# v1.net
KiCad netlist of a schematic drawn in EAGLE
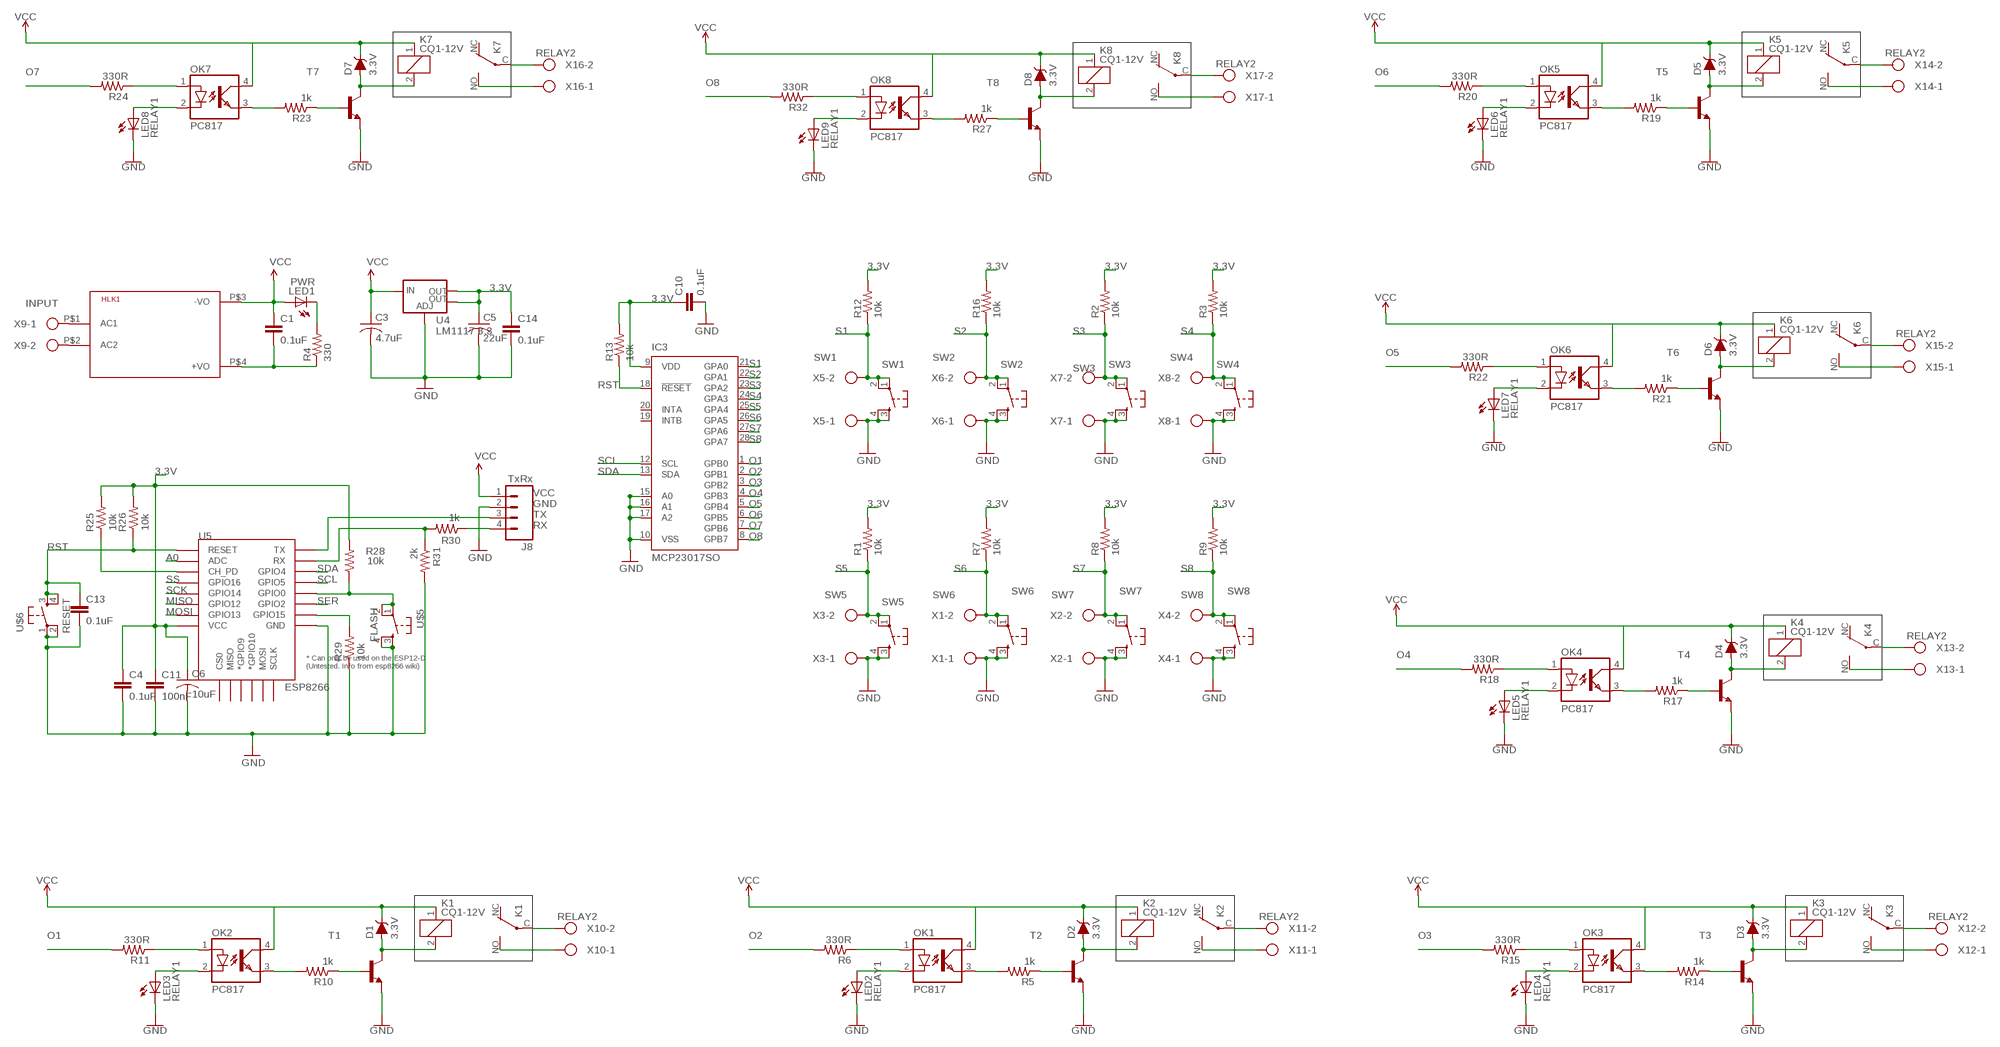
[diagram p0: schematic, sheet 1]

(export (version "E")
  (design (tool "Eeschema 10.0.6"))
  (components
    (comp (ref "C1")
      (value "0.1uF")
      (footprint "eagle-import:0805")
      (libsource (lib "eagle-import") (part "CAP0805"))
    )
    (comp (ref "C3")
      (value "4.7uF")
      (footprint "eagle-import:C1206")
      (libsource (lib "eagle-import") (part "C-USC1206"))
    )
    (comp (ref "C4")
      (value "0.1uF")
      (footprint "eagle-import:0805")
      (libsource (lib "eagle-import") (part "CAP0805"))
    )
    (comp (ref "C5")
      (value "22uF")
      (footprint "eagle-import:C1206")
      (libsource (lib "eagle-import") (part "C-USC1206"))
    )
    (comp (ref "C6")
      (value "10uF")
      (footprint "eagle-import:C1206")
      (libsource (lib "eagle-import") (part "C-USC1206"))
    )
    (comp (ref "C10")
      (value "0.1uF")
      (footprint "eagle-import:0805")
      (libsource (lib "eagle-import") (part "CAP0805"))
    )
    (comp (ref "C11")
      (value "100nF")
      (footprint "eagle-import:0805")
      (libsource (lib "eagle-import") (part "CAP0805"))
    )
    (comp (ref "C13")
      (value "0.1uF")
      (footprint "eagle-import:0805")
      (libsource (lib "eagle-import") (part "CAP0805"))
    )
    (comp (ref "C14")
      (value "0.1uF")
      (footprint "eagle-import:0805")
      (libsource (lib "eagle-import") (part "CAP0805"))
    )
    (comp (ref "D1")
      (value "3.3V")
      (footprint "eagle-import:SOD-323")
      (libsource (lib "eagle-import") (part "DIODE-ZENER-MM3Z3V3T1G"))
    )
    (comp (ref "D2")
      (value "3.3V")
      (footprint "eagle-import:SOD-323")
      (libsource (lib "eagle-import") (part "DIODE-ZENER-MM3Z3V3T1G"))
    )
    (comp (ref "D3")
      (value "3.3V")
      (footprint "eagle-import:SOD-323")
      (libsource (lib "eagle-import") (part "DIODE-ZENER-MM3Z3V3T1G"))
    )
    (comp (ref "D4")
      (value "3.3V")
      (footprint "eagle-import:SOD-323")
      (libsource (lib "eagle-import") (part "DIODE-ZENER-MM3Z3V3T1G"))
    )
    (comp (ref "D5")
      (value "3.3V")
      (footprint "eagle-import:SOD-323")
      (libsource (lib "eagle-import") (part "DIODE-ZENER-MM3Z3V3T1G"))
    )
    (comp (ref "D6")
      (value "3.3V")
      (footprint "eagle-import:SOD-323")
      (libsource (lib "eagle-import") (part "DIODE-ZENER-MM3Z3V3T1G"))
    )
    (comp (ref "D7")
      (value "3.3V")
      (footprint "eagle-import:SOD-323")
      (libsource (lib "eagle-import") (part "DIODE-ZENER-MM3Z3V3T1G"))
    )
    (comp (ref "D8")
      (value "3.3V")
      (footprint "eagle-import:SOD-323")
      (libsource (lib "eagle-import") (part "DIODE-ZENER-MM3Z3V3T1G"))
    )
    (comp (ref "HLK1")
      (value "HLK-PM013W")
      (footprint "eagle-import:HLK-PM01")
      (libsource (lib "eagle-import") (part "HLK-PM013W"))
    )
    (comp (ref "IC3")
      (value "MCP23017SO")
      (footprint "eagle-import:SO28W")
      (fields (field (name "MF") "MICROCHIP") (field (name "MPN") "MCP23017-E/SO"))
      (libsource (lib "eagle-import") (part "MCP23017SO"))
    )
    (comp (ref "J8")
      (value "TxRx")
      (footprint "eagle-import:MOLEX-1X4")
      (libsource (lib "eagle-import") (part "M04POLAR"))
    )
    (comp (ref "K1")
      (value "CQ1-12V")
      (footprint "eagle-import:CQ1")
      (libsource (lib "eagle-import") (part "CQ1-12V"))
    )
    (comp (ref "K2")
      (value "CQ1-12V")
      (footprint "eagle-import:CQ1")
      (libsource (lib "eagle-import") (part "CQ1-12V"))
    )
    (comp (ref "K3")
      (value "CQ1-12V")
      (footprint "eagle-import:CQ1")
      (libsource (lib "eagle-import") (part "CQ1-12V"))
    )
    (comp (ref "K4")
      (value "CQ1-12V")
      (footprint "eagle-import:CQ1")
      (libsource (lib "eagle-import") (part "CQ1-12V"))
    )
    (comp (ref "K5")
      (value "CQ1-12V")
      (footprint "eagle-import:CQ1")
      (libsource (lib "eagle-import") (part "CQ1-12V"))
    )
    (comp (ref "K6")
      (value "CQ1-12V")
      (footprint "eagle-import:CQ1")
      (libsource (lib "eagle-import") (part "CQ1-12V"))
    )
    (comp (ref "K7")
      (value "CQ1-12V")
      (footprint "eagle-import:CQ1")
      (libsource (lib "eagle-import") (part "CQ1-12V"))
    )
    (comp (ref "K8")
      (value "CQ1-12V")
      (footprint "eagle-import:CQ1")
      (libsource (lib "eagle-import") (part "CQ1-12V"))
    )
    (comp (ref "LED1")
      (value "PWR")
      (footprint "eagle-import:CHIP-LED0805")
      (libsource (lib "eagle-import") (part "LEDCHIP-LED0805"))
    )
    (comp (ref "LED2")
      (value "RELAY1")
      (footprint "eagle-import:CHIP-LED0805")
      (libsource (lib "eagle-import") (part "LEDCHIP-LED0805"))
    )
    (comp (ref "LED3")
      (value "RELAY1")
      (footprint "eagle-import:CHIP-LED0805")
      (libsource (lib "eagle-import") (part "LEDCHIP-LED0805"))
    )
    (comp (ref "LED4")
      (value "RELAY1")
      (footprint "eagle-import:CHIP-LED0805")
      (libsource (lib "eagle-import") (part "LEDCHIP-LED0805"))
    )
    (comp (ref "LED5")
      (value "RELAY1")
      (footprint "eagle-import:CHIP-LED0805")
      (libsource (lib "eagle-import") (part "LEDCHIP-LED0805"))
    )
    (comp (ref "LED6")
      (value "RELAY1")
      (footprint "eagle-import:CHIP-LED0805")
      (libsource (lib "eagle-import") (part "LEDCHIP-LED0805"))
    )
    (comp (ref "LED7")
      (value "RELAY1")
      (footprint "eagle-import:CHIP-LED0805")
      (libsource (lib "eagle-import") (part "LEDCHIP-LED0805"))
    )
    (comp (ref "LED8")
      (value "RELAY1")
      (footprint "eagle-import:CHIP-LED0805")
      (libsource (lib "eagle-import") (part "LEDCHIP-LED0805"))
    )
    (comp (ref "LED9")
      (value "RELAY1")
      (footprint "eagle-import:CHIP-LED0805")
      (libsource (lib "eagle-import") (part "LEDCHIP-LED0805"))
    )
    (comp (ref "OK1")
      (value "PC817")
      (footprint "eagle-import:DIL04")
      (fields (field (name "MPN") "PC817X4J000F"))
      (libsource (lib "eagle-import") (part "PC817"))
    )
    (comp (ref "OK2")
      (value "PC817")
      (footprint "eagle-import:DIL04")
      (fields (field (name "MPN") "PC817X4J000F"))
      (libsource (lib "eagle-import") (part "PC817"))
    )
    (comp (ref "OK3")
      (value "PC817")
      (footprint "eagle-import:DIL04")
      (fields (field (name "MPN") "PC817X4J000F"))
      (libsource (lib "eagle-import") (part "PC817"))
    )
    (comp (ref "OK4")
      (value "PC817")
      (footprint "eagle-import:DIL04")
      (fields (field (name "MPN") "PC817X4J000F"))
      (libsource (lib "eagle-import") (part "PC817"))
    )
    (comp (ref "OK5")
      (value "PC817")
      (footprint "eagle-import:DIL04")
      (fields (field (name "MPN") "PC817X4J000F"))
      (libsource (lib "eagle-import") (part "PC817"))
    )
    (comp (ref "OK6")
      (value "PC817")
      (footprint "eagle-import:DIL04")
      (fields (field (name "MPN") "PC817X4J000F"))
      (libsource (lib "eagle-import") (part "PC817"))
    )
    (comp (ref "OK7")
      (value "PC817")
      (footprint "eagle-import:DIL04")
      (fields (field (name "MPN") "PC817X4J000F"))
      (libsource (lib "eagle-import") (part "PC817"))
    )
    (comp (ref "OK8")
      (value "PC817")
      (footprint "eagle-import:DIL04")
      (fields (field (name "MPN") "PC817X4J000F"))
      (libsource (lib "eagle-import") (part "PC817"))
    )
    (comp (ref "R1")
      (value "10k")
      (footprint "eagle-import:0805")
      (libsource (lib "eagle-import") (part "RESISTOR0805-RES"))
    )
    (comp (ref "R2")
      (value "10k")
      (footprint "eagle-import:0805")
      (libsource (lib "eagle-import") (part "RESISTOR0805-RES"))
    )
    (comp (ref "R3")
      (value "10k")
      (footprint "eagle-import:0805")
      (libsource (lib "eagle-import") (part "RESISTOR0805-RES"))
    )
    (comp (ref "R4")
      (value "330")
      (footprint "eagle-import:0805")
      (libsource (lib "eagle-import") (part "RESISTOR0805-RES"))
    )
    (comp (ref "R5")
      (value "1k")
      (footprint "eagle-import:0805")
      (libsource (lib "eagle-import") (part "RESISTOR0805-RES"))
    )
    (comp (ref "R6")
      (value "330R")
      (footprint "eagle-import:0805")
      (libsource (lib "eagle-import") (part "RESISTOR0805-RES"))
    )
    (comp (ref "R7")
      (value "10k")
      (footprint "eagle-import:0805")
      (libsource (lib "eagle-import") (part "RESISTOR0805-RES"))
    )
    (comp (ref "R8")
      (value "10k")
      (footprint "eagle-import:0805")
      (libsource (lib "eagle-import") (part "RESISTOR0805-RES"))
    )
    (comp (ref "R9")
      (value "10k")
      (footprint "eagle-import:0805")
      (libsource (lib "eagle-import") (part "RESISTOR0805-RES"))
    )
    (comp (ref "R10")
      (value "1k")
      (footprint "eagle-import:0805")
      (libsource (lib "eagle-import") (part "RESISTOR0805-RES"))
    )
    (comp (ref "R11")
      (value "330R")
      (footprint "eagle-import:0805")
      (libsource (lib "eagle-import") (part "RESISTOR0805-RES"))
    )
    (comp (ref "R12")
      (value "10k")
      (footprint "eagle-import:0805")
      (libsource (lib "eagle-import") (part "RESISTOR0805-RES"))
    )
    (comp (ref "R13")
      (value "10k")
      (footprint "eagle-import:0805")
      (libsource (lib "eagle-import") (part "RESISTOR0805-RES"))
    )
    (comp (ref "R14")
      (value "1k")
      (footprint "eagle-import:0805")
      (libsource (lib "eagle-import") (part "RESISTOR0805-RES"))
    )
    (comp (ref "R15")
      (value "330R")
      (footprint "eagle-import:0805")
      (libsource (lib "eagle-import") (part "RESISTOR0805-RES"))
    )
    (comp (ref "R16")
      (value "10k")
      (footprint "eagle-import:0805")
      (libsource (lib "eagle-import") (part "RESISTOR0805-RES"))
    )
    (comp (ref "R17")
      (value "1k")
      (footprint "eagle-import:0805")
      (libsource (lib "eagle-import") (part "RESISTOR0805-RES"))
    )
    (comp (ref "R18")
      (value "330R")
      (footprint "eagle-import:0805")
      (libsource (lib "eagle-import") (part "RESISTOR0805-RES"))
    )
    (comp (ref "R19")
      (value "1k")
      (footprint "eagle-import:0805")
      (libsource (lib "eagle-import") (part "RESISTOR0805-RES"))
    )
    (comp (ref "R20")
      (value "330R")
      (footprint "eagle-import:0805")
      (libsource (lib "eagle-import") (part "RESISTOR0805-RES"))
    )
    (comp (ref "R21")
      (value "1k")
      (footprint "eagle-import:0805")
      (libsource (lib "eagle-import") (part "RESISTOR0805-RES"))
    )
    (comp (ref "R22")
      (value "330R")
      (footprint "eagle-import:0805")
      (libsource (lib "eagle-import") (part "RESISTOR0805-RES"))
    )
    (comp (ref "R23")
      (value "1k")
      (footprint "eagle-import:0805")
      (libsource (lib "eagle-import") (part "RESISTOR0805-RES"))
    )
    (comp (ref "R24")
      (value "330R")
      (footprint "eagle-import:0805")
      (libsource (lib "eagle-import") (part "RESISTOR0805-RES"))
    )
    (comp (ref "R25")
      (value "10k")
      (footprint "eagle-import:0805")
      (libsource (lib "eagle-import") (part "RESISTOR0805-RES"))
    )
    (comp (ref "R26")
      (value "10k")
      (footprint "eagle-import:0805")
      (libsource (lib "eagle-import") (part "RESISTOR0805-RES"))
    )
    (comp (ref "R27")
      (value "1k")
      (footprint "eagle-import:0805")
      (libsource (lib "eagle-import") (part "RESISTOR0805-RES"))
    )
    (comp (ref "R28")
      (value "10k")
      (footprint "eagle-import:0805")
      (libsource (lib "eagle-import") (part "RESISTOR0805-RES"))
    )
    (comp (ref "R29")
      (value "10k")
      (footprint "eagle-import:0805")
      (libsource (lib "eagle-import") (part "RESISTOR0805-RES"))
    )
    (comp (ref "R30")
      (value "1k")
      (footprint "eagle-import:0805")
      (libsource (lib "eagle-import") (part "RESISTOR0805-RES"))
    )
    (comp (ref "R31")
      (value "2k")
      (footprint "eagle-import:0805")
      (libsource (lib "eagle-import") (part "RESISTOR0805-RES"))
    )
    (comp (ref "R32")
      (value "330R")
      (footprint "eagle-import:0805")
      (libsource (lib "eagle-import") (part "RESISTOR0805-RES"))
    )
    (comp (ref "T1")
      (value "-NPN-SOT23-BEC")
      (footprint "eagle-import:SOT23-BEC")
      (libsource (lib "eagle-import") (part "-NPN-SOT23-BEC"))
    )
    (comp (ref "T2")
      (value "-NPN-SOT23-BEC")
      (footprint "eagle-import:SOT23-BEC")
      (libsource (lib "eagle-import") (part "-NPN-SOT23-BEC"))
    )
    (comp (ref "T3")
      (value "-NPN-SOT23-BEC")
      (footprint "eagle-import:SOT23-BEC")
      (libsource (lib "eagle-import") (part "-NPN-SOT23-BEC"))
    )
    (comp (ref "T4")
      (value "-NPN-SOT23-BEC")
      (footprint "eagle-import:SOT23-BEC")
      (libsource (lib "eagle-import") (part "-NPN-SOT23-BEC"))
    )
    (comp (ref "T5")
      (value "-NPN-SOT23-BEC")
      (footprint "eagle-import:SOT23-BEC")
      (libsource (lib "eagle-import") (part "-NPN-SOT23-BEC"))
    )
    (comp (ref "T6")
      (value "-NPN-SOT23-BEC")
      (footprint "eagle-import:SOT23-BEC")
      (libsource (lib "eagle-import") (part "-NPN-SOT23-BEC"))
    )
    (comp (ref "T7")
      (value "-NPN-SOT23-BEC")
      (footprint "eagle-import:SOT23-BEC")
      (libsource (lib "eagle-import") (part "-NPN-SOT23-BEC"))
    )
    (comp (ref "T8")
      (value "-NPN-SOT23-BEC")
      (footprint "eagle-import:SOT23-BEC")
      (libsource (lib "eagle-import") (part "-NPN-SOT23-BEC"))
    )
    (comp (ref "U$1")
      (value "SW1")
      (footprint "eagle-import:TAC-SWITCH-PTH")
      (libsource (lib "eagle-import") (part "TACTILE-SWITCH-PTH"))
    )
    (comp (ref "U$2")
      (value "SW2")
      (footprint "eagle-import:TAC-SWITCH-PTH")
      (libsource (lib "eagle-import") (part "TACTILE-SWITCH-PTH"))
    )
    (comp (ref "U$3")
      (value "SW5")
      (footprint "eagle-import:TAC-SWITCH-PTH")
      (libsource (lib "eagle-import") (part "TACTILE-SWITCH-PTH"))
    )
    (comp (ref "U$4")
      (value "SW3")
      (footprint "eagle-import:TAC-SWITCH-PTH")
      (libsource (lib "eagle-import") (part "TACTILE-SWITCH-PTH"))
    )
    (comp (ref "U$5")
      (value "FLASH")
      (footprint "eagle-import:TAC-SWITCH-PTH")
      (libsource (lib "eagle-import") (part "TACTILE-SWITCH-PTH"))
    )
    (comp (ref "U$6")
      (value "RESET")
      (footprint "eagle-import:TAC-SWITCH-PTH")
      (libsource (lib "eagle-import") (part "TACTILE-SWITCH-PTH"))
    )
    (comp (ref "U$7")
      (value "SW4")
      (footprint "eagle-import:TAC-SWITCH-PTH")
      (libsource (lib "eagle-import") (part "TACTILE-SWITCH-PTH"))
    )
    (comp (ref "U$8")
      (value "SW6")
      (footprint "eagle-import:TAC-SWITCH-PTH")
      (libsource (lib "eagle-import") (part "TACTILE-SWITCH-PTH"))
    )
    (comp (ref "U$9")
      (value "SW7")
      (footprint "eagle-import:TAC-SWITCH-PTH")
      (libsource (lib "eagle-import") (part "TACTILE-SWITCH-PTH"))
    )
    (comp (ref "U$10")
      (value "SW8")
      (footprint "eagle-import:TAC-SWITCH-PTH")
      (libsource (lib "eagle-import") (part "TACTILE-SWITCH-PTH"))
    )
    (comp (ref "U4")
      (value "LM1117 3.3")
      (footprint "eagle-import:SOT223")
      (libsource (lib "eagle-import") (part "V_REG_LM1117SOT223"))
    )
    (comp (ref "U5")
      (value "ESP8266")
      (footprint "eagle-import:ESP12E-SMD")
      (libsource (lib "eagle-import") (part "ESP12ESMD"))
    )
    (comp (ref "X1")
      (value "SW6")
      (footprint "eagle-import:W237-102")
      (fields (field (name "MPN") "237-102"))
      (libsource (lib "eagle-import") (part "W237-102"))
    )
    (comp (ref "X2")
      (value "SW7")
      (footprint "eagle-import:W237-102")
      (fields (field (name "MPN") "237-102"))
      (libsource (lib "eagle-import") (part "W237-102"))
    )
    (comp (ref "X3")
      (value "SW5")
      (footprint "eagle-import:W237-102")
      (fields (field (name "MPN") "237-102"))
      (libsource (lib "eagle-import") (part "W237-102"))
    )
    (comp (ref "X4")
      (value "SW8")
      (footprint "eagle-import:W237-102")
      (fields (field (name "MPN") "237-102"))
      (libsource (lib "eagle-import") (part "W237-102"))
    )
    (comp (ref "X5")
      (value "SW1")
      (footprint "eagle-import:W237-102")
      (fields (field (name "MPN") "237-102"))
      (libsource (lib "eagle-import") (part "W237-102"))
    )
    (comp (ref "X6")
      (value "SW2")
      (footprint "eagle-import:W237-102")
      (fields (field (name "MPN") "237-102"))
      (libsource (lib "eagle-import") (part "W237-102"))
    )
    (comp (ref "X7")
      (value "SW3")
      (footprint "eagle-import:W237-102")
      (fields (field (name "MPN") "237-102"))
      (libsource (lib "eagle-import") (part "W237-102"))
    )
    (comp (ref "X8")
      (value "SW4")
      (footprint "eagle-import:W237-102")
      (fields (field (name "MPN") "237-102"))
      (libsource (lib "eagle-import") (part "W237-102"))
    )
    (comp (ref "X9")
      (value "INPUT")
      (footprint "eagle-import:W237-102")
      (fields (field (name "MPN") "237-102"))
      (libsource (lib "eagle-import") (part "W237-102"))
    )
    (comp (ref "X10")
      (value "RELAY2")
      (footprint "eagle-import:W237-102")
      (fields (field (name "MPN") "237-102"))
      (libsource (lib "eagle-import") (part "W237-102"))
    )
    (comp (ref "X11")
      (value "RELAY2")
      (footprint "eagle-import:W237-102")
      (fields (field (name "MPN") "237-102"))
      (libsource (lib "eagle-import") (part "W237-102"))
    )
    (comp (ref "X12")
      (value "RELAY2")
      (footprint "eagle-import:W237-102")
      (fields (field (name "MPN") "237-102"))
      (libsource (lib "eagle-import") (part "W237-102"))
    )
    (comp (ref "X13")
      (value "RELAY2")
      (footprint "eagle-import:W237-102")
      (fields (field (name "MPN") "237-102"))
      (libsource (lib "eagle-import") (part "W237-102"))
    )
    (comp (ref "X14")
      (value "RELAY2")
      (footprint "eagle-import:W237-102")
      (fields (field (name "MPN") "237-102"))
      (libsource (lib "eagle-import") (part "W237-102"))
    )
    (comp (ref "X15")
      (value "RELAY2")
      (footprint "eagle-import:W237-102")
      (fields (field (name "MPN") "237-102"))
      (libsource (lib "eagle-import") (part "W237-102"))
    )
    (comp (ref "X16")
      (value "RELAY2")
      (footprint "eagle-import:W237-102")
      (fields (field (name "MPN") "237-102"))
      (libsource (lib "eagle-import") (part "W237-102"))
    )
    (comp (ref "X17")
      (value "RELAY2")
      (footprint "eagle-import:W237-102")
      (fields (field (name "MPN") "237-102"))
      (libsource (lib "eagle-import") (part "W237-102"))
    )
  )
  (nets
    (net (code "1") (name "/3.3V") (class "Default")
      (node (ref "C10") (pin "1") (pinfunction "1_1") (pintype "passive"))
      (node (ref "C11") (pin "1") (pinfunction "1_1") (pintype "passive"))
      (node (ref "C14") (pin "1") (pinfunction "1_1") (pintype "passive"))
      (node (ref "C4") (pin "1") (pinfunction "1_1") (pintype "passive"))
      (node (ref "C5") (pin "1") (pinfunction "1_1") (pintype "passive"))
      (node (ref "C6") (pin "1") (pinfunction "1_1") (pintype "passive"))
      (node (ref "IC3") (pin "9") (pinfunction "VDD_9") (pintype "power_in"))
      (node (ref "R1") (pin "2") (pinfunction "2_2") (pintype "passive"))
      (node (ref "R12") (pin "2") (pinfunction "2_2") (pintype "passive"))
      (node (ref "R13") (pin "2") (pinfunction "2_2") (pintype "passive"))
      (node (ref "R16") (pin "2") (pinfunction "2_2") (pintype "passive"))
      (node (ref "R2") (pin "2") (pinfunction "2_2") (pintype "passive"))
      (node (ref "R25") (pin "2") (pinfunction "2_2") (pintype "passive"))
      (node (ref "R26") (pin "2") (pinfunction "2_2") (pintype "passive"))
      (node (ref "R28") (pin "2") (pinfunction "2_2") (pintype "passive"))
      (node (ref "R3") (pin "2") (pinfunction "2_2") (pintype "passive"))
      (node (ref "R7") (pin "2") (pinfunction "2_2") (pintype "passive"))
      (node (ref "R8") (pin "2") (pinfunction "2_2") (pintype "passive"))
      (node (ref "R9") (pin "2") (pinfunction "2_2") (pintype "passive"))
      (node (ref "U4") (pin "2") (pinfunction "OUT_2") (pintype "output"))
      (node (ref "U4") (pin "4") (pinfunction "OUT_4") (pintype "output"))
      (node (ref "U5") (pin "VCC") (pinfunction "VCC_VCC") (pintype "bidirectional"))
    )
    (net (code "2") (name "/A0") (class "Default")
      (node (ref "U5") (pin "ADC") (pinfunction "ADC_ADC") (pintype "bidirectional"))
    )
    (net (code "3") (name "/MISO") (class "Default")
      (node (ref "U5") (pin "GPIO12") (pinfunction "GPIO12_GPIO12") (pintype "bidirectional"))
    )
    (net (code "4") (name "/MOSI") (class "Default")
      (node (ref "U5") (pin "GPIO13") (pinfunction "GPIO13_GPIO13") (pintype "bidirectional"))
    )
    (net (code "5") (name "/O1") (class "Default")
      (node (ref "IC3") (pin "1") (pinfunction "GPB0_1") (pintype "bidirectional"))
      (node (ref "R11") (pin "2") (pinfunction "2_2") (pintype "passive"))
    )
    (net (code "6") (name "/O2") (class "Default")
      (node (ref "IC3") (pin "2") (pinfunction "GPB1_2") (pintype "bidirectional"))
      (node (ref "R6") (pin "2") (pinfunction "2_2") (pintype "passive"))
    )
    (net (code "7") (name "/O3") (class "Default")
      (node (ref "IC3") (pin "3") (pinfunction "GPB2_3") (pintype "bidirectional"))
      (node (ref "R15") (pin "2") (pinfunction "2_2") (pintype "passive"))
    )
    (net (code "8") (name "/O4") (class "Default")
      (node (ref "IC3") (pin "4") (pinfunction "GPB3_4") (pintype "bidirectional"))
      (node (ref "R18") (pin "2") (pinfunction "2_2") (pintype "passive"))
    )
    (net (code "9") (name "/O5") (class "Default")
      (node (ref "IC3") (pin "5") (pinfunction "GPB4_5") (pintype "bidirectional"))
      (node (ref "R22") (pin "2") (pinfunction "2_2") (pintype "passive"))
    )
    (net (code "10") (name "/O6") (class "Default")
      (node (ref "IC3") (pin "6") (pinfunction "GPB5_6") (pintype "bidirectional"))
      (node (ref "R20") (pin "2") (pinfunction "2_2") (pintype "passive"))
    )
    (net (code "11") (name "/O7") (class "Default")
      (node (ref "IC3") (pin "7") (pinfunction "GPB6_7") (pintype "bidirectional"))
      (node (ref "R24") (pin "2") (pinfunction "2_2") (pintype "passive"))
    )
    (net (code "12") (name "/O8") (class "Default")
      (node (ref "IC3") (pin "8") (pinfunction "GPB7_8") (pintype "bidirectional"))
      (node (ref "R32") (pin "2") (pinfunction "2_2") (pintype "passive"))
    )
    (net (code "13") (name "/RST") (class "Default")
      (node (ref "C13") (pin "1") (pinfunction "1_1") (pintype "passive"))
      (node (ref "IC3") (pin "18") (pinfunction "~{RESET}_18") (pintype "input"))
      (node (ref "R13") (pin "1") (pinfunction "1_1") (pintype "passive"))
      (node (ref "R26") (pin "1") (pinfunction "1_1") (pintype "passive"))
      (node (ref "U$6") (pin "3") (pinfunction "3_3") (pintype "passive"))
      (node (ref "U$6") (pin "4") (pinfunction "4_4") (pintype "passive"))
      (node (ref "U5") (pin "RESET") (pinfunction "RESET_RESET") (pintype "bidirectional"))
    )
    (net (code "14") (name "/RX") (class "Default")
      (node (ref "J8") (pin "4") (pinfunction "4_4") (pintype "passive"))
      (node (ref "R30") (pin "1") (pinfunction "1_1") (pintype "passive"))
    )
    (net (code "15") (name "/S1") (class "Default")
      (node (ref "IC3") (pin "21") (pinfunction "GPA0_21") (pintype "bidirectional"))
      (node (ref "R12") (pin "1") (pinfunction "1_1") (pintype "passive"))
      (node (ref "U$1") (pin "1") (pinfunction "1_1") (pintype "passive"))
      (node (ref "U$1") (pin "2") (pinfunction "2_2") (pintype "passive"))
      (node (ref "X5") (pin "2") (pinfunction "KL_2") (pintype "passive"))
    )
    (net (code "16") (name "/S2") (class "Default")
      (node (ref "IC3") (pin "22") (pinfunction "GPA1_22") (pintype "bidirectional"))
      (node (ref "R16") (pin "1") (pinfunction "1_1") (pintype "passive"))
      (node (ref "U$2") (pin "1") (pinfunction "1_1") (pintype "passive"))
      (node (ref "U$2") (pin "2") (pinfunction "2_2") (pintype "passive"))
      (node (ref "X6") (pin "2") (pinfunction "KL_2") (pintype "passive"))
    )
    (net (code "17") (name "/S3") (class "Default")
      (node (ref "IC3") (pin "23") (pinfunction "GPA2_23") (pintype "bidirectional"))
      (node (ref "R2") (pin "1") (pinfunction "1_1") (pintype "passive"))
      (node (ref "U$4") (pin "1") (pinfunction "1_1") (pintype "passive"))
      (node (ref "U$4") (pin "2") (pinfunction "2_2") (pintype "passive"))
      (node (ref "X7") (pin "2") (pinfunction "KL_2") (pintype "passive"))
    )
    (net (code "18") (name "/S4") (class "Default")
      (node (ref "IC3") (pin "24") (pinfunction "GPA3_24") (pintype "bidirectional"))
      (node (ref "R3") (pin "1") (pinfunction "1_1") (pintype "passive"))
      (node (ref "U$7") (pin "1") (pinfunction "1_1") (pintype "passive"))
      (node (ref "U$7") (pin "2") (pinfunction "2_2") (pintype "passive"))
      (node (ref "X8") (pin "2") (pinfunction "KL_2") (pintype "passive"))
    )
    (net (code "19") (name "/S5") (class "Default")
      (node (ref "IC3") (pin "25") (pinfunction "GPA4_25") (pintype "bidirectional"))
      (node (ref "R1") (pin "1") (pinfunction "1_1") (pintype "passive"))
      (node (ref "U$3") (pin "1") (pinfunction "1_1") (pintype "passive"))
      (node (ref "U$3") (pin "2") (pinfunction "2_2") (pintype "passive"))
      (node (ref "X3") (pin "2") (pinfunction "KL_2") (pintype "passive"))
    )
    (net (code "20") (name "/S6") (class "Default")
      (node (ref "IC3") (pin "26") (pinfunction "GPA5_26") (pintype "bidirectional"))
      (node (ref "R7") (pin "1") (pinfunction "1_1") (pintype "passive"))
      (node (ref "U$8") (pin "1") (pinfunction "1_1") (pintype "passive"))
      (node (ref "U$8") (pin "2") (pinfunction "2_2") (pintype "passive"))
      (node (ref "X1") (pin "2") (pinfunction "KL_2") (pintype "passive"))
    )
    (net (code "21") (name "/S7") (class "Default")
      (node (ref "IC3") (pin "27") (pinfunction "GPA6_27") (pintype "bidirectional"))
      (node (ref "R8") (pin "1") (pinfunction "1_1") (pintype "passive"))
      (node (ref "U$9") (pin "1") (pinfunction "1_1") (pintype "passive"))
      (node (ref "U$9") (pin "2") (pinfunction "2_2") (pintype "passive"))
      (node (ref "X2") (pin "2") (pinfunction "KL_2") (pintype "passive"))
    )
    (net (code "22") (name "/S8") (class "Default")
      (node (ref "IC3") (pin "28") (pinfunction "GPA7_28") (pintype "bidirectional"))
      (node (ref "R9") (pin "1") (pinfunction "1_1") (pintype "passive"))
      (node (ref "U$10") (pin "1") (pinfunction "1_1") (pintype "passive"))
      (node (ref "U$10") (pin "2") (pinfunction "2_2") (pintype "passive"))
      (node (ref "X4") (pin "2") (pinfunction "KL_2") (pintype "passive"))
    )
    (net (code "23") (name "/SCK") (class "Default")
      (node (ref "U5") (pin "GPIO14") (pinfunction "GPIO14_GPIO14") (pintype "bidirectional"))
    )
    (net (code "24") (name "/SCL") (class "Default")
      (node (ref "IC3") (pin "12") (pinfunction "SCL_12") (pintype "input"))
      (node (ref "U5") (pin "GPIO5") (pinfunction "GPIO5_GPIO5") (pintype "bidirectional"))
    )
    (net (code "25") (name "/SDA") (class "Default")
      (node (ref "IC3") (pin "13") (pinfunction "SDA_13") (pintype "bidirectional"))
      (node (ref "U5") (pin "GPIO4") (pinfunction "GPIO4_GPIO4") (pintype "bidirectional"))
    )
    (net (code "26") (name "/SER") (class "Default")
      (node (ref "U5") (pin "GPIO2") (pinfunction "GPIO2_GPIO2") (pintype "bidirectional"))
    )
    (net (code "27") (name "/SS") (class "Default")
      (node (ref "U5") (pin "GPIO16") (pinfunction "GPIO16_GPIO16") (pintype "bidirectional"))
    )
    (net (code "28") (name "/TX") (class "Default")
      (node (ref "J8") (pin "3") (pinfunction "3_3") (pintype "passive"))
      (node (ref "U5") (pin "TXD0") (pinfunction "TX_TXD0") (pintype "bidirectional"))
    )
    (net (code "29") (name "GND") (class "Default")
      (node (ref "C10") (pin "2") (pinfunction "2_2") (pintype "passive"))
      (node (ref "C11") (pin "2") (pinfunction "2_2") (pintype "passive"))
      (node (ref "C13") (pin "2") (pinfunction "2_2") (pintype "passive"))
      (node (ref "C14") (pin "2") (pinfunction "2_2") (pintype "passive"))
      (node (ref "C3") (pin "2") (pinfunction "2_2") (pintype "passive"))
      (node (ref "C4") (pin "2") (pinfunction "2_2") (pintype "passive"))
      (node (ref "C5") (pin "2") (pinfunction "2_2") (pintype "passive"))
      (node (ref "C6") (pin "2") (pinfunction "2_2") (pintype "passive"))
      (node (ref "IC3") (pin "10") (pinfunction "VSS_10") (pintype "power_in"))
      (node (ref "IC3") (pin "15") (pinfunction "A0_15") (pintype "input"))
      (node (ref "IC3") (pin "16") (pinfunction "A1_16") (pintype "input"))
      (node (ref "IC3") (pin "17") (pinfunction "A2_17") (pintype "input"))
      (node (ref "J8") (pin "2") (pinfunction "2_2") (pintype "passive"))
      (node (ref "LED2") (pin "C") (pinfunction "C_C") (pintype "passive"))
      (node (ref "LED3") (pin "C") (pinfunction "C_C") (pintype "passive"))
      (node (ref "LED4") (pin "C") (pinfunction "C_C") (pintype "passive"))
      (node (ref "LED5") (pin "C") (pinfunction "C_C") (pintype "passive"))
      (node (ref "LED6") (pin "C") (pinfunction "C_C") (pintype "passive"))
      (node (ref "LED7") (pin "C") (pinfunction "C_C") (pintype "passive"))
      (node (ref "LED8") (pin "C") (pinfunction "C_C") (pintype "passive"))
      (node (ref "LED9") (pin "C") (pinfunction "C_C") (pintype "passive"))
      (node (ref "R29") (pin "1") (pinfunction "1_1") (pintype "passive"))
      (node (ref "R31") (pin "2") (pinfunction "2_2") (pintype "passive"))
      (node (ref "T1") (pin "E") (pinfunction "E_E") (pintype "passive"))
      (node (ref "T2") (pin "E") (pinfunction "E_E") (pintype "passive"))
      (node (ref "T3") (pin "E") (pinfunction "E_E") (pintype "passive"))
      (node (ref "T4") (pin "E") (pinfunction "E_E") (pintype "passive"))
      (node (ref "T5") (pin "E") (pinfunction "E_E") (pintype "passive"))
      (node (ref "T6") (pin "E") (pinfunction "E_E") (pintype "passive"))
      (node (ref "T7") (pin "E") (pinfunction "E_E") (pintype "passive"))
      (node (ref "T8") (pin "E") (pinfunction "E_E") (pintype "passive"))
      (node (ref "U$1") (pin "3") (pinfunction "3_3") (pintype "passive"))
      (node (ref "U$1") (pin "4") (pinfunction "4_4") (pintype "passive"))
      (node (ref "U$10") (pin "3") (pinfunction "3_3") (pintype "passive"))
      (node (ref "U$10") (pin "4") (pinfunction "4_4") (pintype "passive"))
      (node (ref "U$2") (pin "3") (pinfunction "3_3") (pintype "passive"))
      (node (ref "U$2") (pin "4") (pinfunction "4_4") (pintype "passive"))
      (node (ref "U$3") (pin "3") (pinfunction "3_3") (pintype "passive"))
      (node (ref "U$3") (pin "4") (pinfunction "4_4") (pintype "passive"))
      (node (ref "U$4") (pin "3") (pinfunction "3_3") (pintype "passive"))
      (node (ref "U$4") (pin "4") (pinfunction "4_4") (pintype "passive"))
      (node (ref "U$5") (pin "3") (pinfunction "3_3") (pintype "passive"))
      (node (ref "U$5") (pin "4") (pinfunction "4_4") (pintype "passive"))
      (node (ref "U$6") (pin "1") (pinfunction "1_1") (pintype "passive"))
      (node (ref "U$6") (pin "2") (pinfunction "2_2") (pintype "passive"))
      (node (ref "U$7") (pin "3") (pinfunction "3_3") (pintype "passive"))
      (node (ref "U$7") (pin "4") (pinfunction "4_4") (pintype "passive"))
      (node (ref "U$8") (pin "3") (pinfunction "3_3") (pintype "passive"))
      (node (ref "U$8") (pin "4") (pinfunction "4_4") (pintype "passive"))
      (node (ref "U$9") (pin "3") (pinfunction "3_3") (pintype "passive"))
      (node (ref "U$9") (pin "4") (pinfunction "4_4") (pintype "passive"))
      (node (ref "U4") (pin "1") (pinfunction "ADJ_1") (pintype "input"))
      (node (ref "U5") (pin "GND") (pinfunction "GND_GND") (pintype "bidirectional"))
      (node (ref "X1") (pin "1") (pinfunction "KL_1") (pintype "passive"))
      (node (ref "X2") (pin "1") (pinfunction "KL_1") (pintype "passive"))
      (node (ref "X3") (pin "1") (pinfunction "KL_1") (pintype "passive"))
      (node (ref "X4") (pin "1") (pinfunction "KL_1") (pintype "passive"))
      (node (ref "X5") (pin "1") (pinfunction "KL_1") (pintype "passive"))
      (node (ref "X6") (pin "1") (pinfunction "KL_1") (pintype "passive"))
      (node (ref "X7") (pin "1") (pinfunction "KL_1") (pintype "passive"))
      (node (ref "X8") (pin "1") (pinfunction "KL_1") (pintype "passive"))
    )
    (net (code "30") (name "Net-(D1-PadA)") (class "Default")
      (node (ref "D1") (pin "A") (pinfunction "A_A") (pintype "passive"))
      (node (ref "K1") (pin "2") (pinfunction "2_2") (pintype "passive"))
      (node (ref "T1") (pin "C") (pinfunction "C_C") (pintype "passive"))
    )
    (net (code "31") (name "Net-(D2-PadA)") (class "Default")
      (node (ref "D2") (pin "A") (pinfunction "A_A") (pintype "passive"))
      (node (ref "K2") (pin "2") (pinfunction "2_2") (pintype "passive"))
      (node (ref "T2") (pin "C") (pinfunction "C_C") (pintype "passive"))
    )
    (net (code "32") (name "Net-(D3-PadA)") (class "Default")
      (node (ref "D3") (pin "A") (pinfunction "A_A") (pintype "passive"))
      (node (ref "K3") (pin "2") (pinfunction "2_2") (pintype "passive"))
      (node (ref "T3") (pin "C") (pinfunction "C_C") (pintype "passive"))
    )
    (net (code "33") (name "Net-(D4-PadA)") (class "Default")
      (node (ref "D4") (pin "A") (pinfunction "A_A") (pintype "passive"))
      (node (ref "K4") (pin "2") (pinfunction "2_2") (pintype "passive"))
      (node (ref "T4") (pin "C") (pinfunction "C_C") (pintype "passive"))
    )
    (net (code "34") (name "Net-(D5-PadA)") (class "Default")
      (node (ref "D5") (pin "A") (pinfunction "A_A") (pintype "passive"))
      (node (ref "K5") (pin "2") (pinfunction "2_2") (pintype "passive"))
      (node (ref "T5") (pin "C") (pinfunction "C_C") (pintype "passive"))
    )
    (net (code "35") (name "Net-(D6-PadA)") (class "Default")
      (node (ref "D6") (pin "A") (pinfunction "A_A") (pintype "passive"))
      (node (ref "K6") (pin "2") (pinfunction "2_2") (pintype "passive"))
      (node (ref "T6") (pin "C") (pinfunction "C_C") (pintype "passive"))
    )
    (net (code "36") (name "Net-(D7-PadA)") (class "Default")
      (node (ref "D7") (pin "A") (pinfunction "A_A") (pintype "passive"))
      (node (ref "K7") (pin "2") (pinfunction "2_2") (pintype "passive"))
      (node (ref "T7") (pin "C") (pinfunction "C_C") (pintype "passive"))
    )
    (net (code "37") (name "Net-(D8-PadA)") (class "Default")
      (node (ref "D8") (pin "A") (pinfunction "A_A") (pintype "passive"))
      (node (ref "K8") (pin "2") (pinfunction "2_2") (pintype "passive"))
      (node (ref "T8") (pin "C") (pinfunction "C_C") (pintype "passive"))
    )
    (net (code "38") (name "Net-(HLK1-+VO)") (class "Default")
      (node (ref "C1") (pin "2") (pinfunction "2_2") (pintype "passive"))
      (node (ref "HLK1") (pin "P$4") (pinfunction "+VO_P$4") (pintype "bidirectional"))
      (node (ref "R4") (pin "1") (pinfunction "1_1") (pintype "passive"))
    )
    (net (code "39") (name "Net-(HLK1-AC1)") (class "Default")
      (node (ref "HLK1") (pin "P$1") (pinfunction "AC1_P$1") (pintype "bidirectional"))
      (node (ref "X9") (pin "1") (pinfunction "KL_1") (pintype "passive"))
    )
    (net (code "40") (name "Net-(HLK1-AC2)") (class "Default")
      (node (ref "HLK1") (pin "P$2") (pinfunction "AC2_P$2") (pintype "bidirectional"))
      (node (ref "X9") (pin "2") (pinfunction "KL_2") (pintype "passive"))
    )
    (net (code "41") (name "Net-(K1B-P)") (class "Default")
      (node (ref "K1") (pin "C") (pinfunction "P_C") (pintype "passive"))
      (node (ref "X10") (pin "2") (pinfunction "KL_2") (pintype "passive"))
    )
    (net (code "42") (name "Net-(K1B-S)") (class "Default")
      (node (ref "K1") (pin "NO") (pinfunction "S_NO") (pintype "passive"))
      (node (ref "X10") (pin "1") (pinfunction "KL_1") (pintype "passive"))
    )
    (net (code "43") (name "Net-(K2B-P)") (class "Default")
      (node (ref "K2") (pin "C") (pinfunction "P_C") (pintype "passive"))
      (node (ref "X11") (pin "2") (pinfunction "KL_2") (pintype "passive"))
    )
    (net (code "44") (name "Net-(K2B-S)") (class "Default")
      (node (ref "K2") (pin "NO") (pinfunction "S_NO") (pintype "passive"))
      (node (ref "X11") (pin "1") (pinfunction "KL_1") (pintype "passive"))
    )
    (net (code "45") (name "Net-(K3B-P)") (class "Default")
      (node (ref "K3") (pin "C") (pinfunction "P_C") (pintype "passive"))
      (node (ref "X12") (pin "2") (pinfunction "KL_2") (pintype "passive"))
    )
    (net (code "46") (name "Net-(K3B-S)") (class "Default")
      (node (ref "K3") (pin "NO") (pinfunction "S_NO") (pintype "passive"))
      (node (ref "X12") (pin "1") (pinfunction "KL_1") (pintype "passive"))
    )
    (net (code "47") (name "Net-(K4B-P)") (class "Default")
      (node (ref "K4") (pin "C") (pinfunction "P_C") (pintype "passive"))
      (node (ref "X13") (pin "2") (pinfunction "KL_2") (pintype "passive"))
    )
    (net (code "48") (name "Net-(K4B-S)") (class "Default")
      (node (ref "K4") (pin "NO") (pinfunction "S_NO") (pintype "passive"))
      (node (ref "X13") (pin "1") (pinfunction "KL_1") (pintype "passive"))
    )
    (net (code "49") (name "Net-(K5B-P)") (class "Default")
      (node (ref "K5") (pin "C") (pinfunction "P_C") (pintype "passive"))
      (node (ref "X14") (pin "2") (pinfunction "KL_2") (pintype "passive"))
    )
    (net (code "50") (name "Net-(K5B-S)") (class "Default")
      (node (ref "K5") (pin "NO") (pinfunction "S_NO") (pintype "passive"))
      (node (ref "X14") (pin "1") (pinfunction "KL_1") (pintype "passive"))
    )
    (net (code "51") (name "Net-(K6B-P)") (class "Default")
      (node (ref "K6") (pin "C") (pinfunction "P_C") (pintype "passive"))
      (node (ref "X15") (pin "2") (pinfunction "KL_2") (pintype "passive"))
    )
    (net (code "52") (name "Net-(K6B-S)") (class "Default")
      (node (ref "K6") (pin "NO") (pinfunction "S_NO") (pintype "passive"))
      (node (ref "X15") (pin "1") (pinfunction "KL_1") (pintype "passive"))
    )
    (net (code "53") (name "Net-(K7B-P)") (class "Default")
      (node (ref "K7") (pin "C") (pinfunction "P_C") (pintype "passive"))
      (node (ref "X16") (pin "2") (pinfunction "KL_2") (pintype "passive"))
    )
    (net (code "54") (name "Net-(K7B-S)") (class "Default")
      (node (ref "K7") (pin "NO") (pinfunction "S_NO") (pintype "passive"))
      (node (ref "X16") (pin "1") (pinfunction "KL_1") (pintype "passive"))
    )
    (net (code "55") (name "Net-(K8B-P)") (class "Default")
      (node (ref "K8") (pin "C") (pinfunction "P_C") (pintype "passive"))
      (node (ref "X17") (pin "2") (pinfunction "KL_2") (pintype "passive"))
    )
    (net (code "56") (name "Net-(K8B-S)") (class "Default")
      (node (ref "K8") (pin "NO") (pinfunction "S_NO") (pintype "passive"))
      (node (ref "X17") (pin "1") (pinfunction "KL_1") (pintype "passive"))
    )
    (net (code "57") (name "Net-(LED1-PadC)") (class "Default")
      (node (ref "LED1") (pin "C") (pinfunction "C_C") (pintype "passive"))
      (node (ref "R4") (pin "2") (pinfunction "2_2") (pintype "passive"))
    )
    (net (code "58") (name "Net-(OK1-A)") (class "Default")
      (node (ref "OK1") (pin "1") (pinfunction "A_1") (pintype "passive"))
      (node (ref "R6") (pin "1") (pinfunction "1_1") (pintype "passive"))
    )
    (net (code "59") (name "Net-(OK1-C)") (class "Default")
      (node (ref "LED2") (pin "A") (pinfunction "A_A") (pintype "passive"))
      (node (ref "OK1") (pin "2") (pinfunction "C_2") (pintype "passive"))
    )
    (net (code "60") (name "Net-(OK1-EMIT)") (class "Default")
      (node (ref "OK1") (pin "3") (pinfunction "EMIT_3") (pintype "passive"))
      (node (ref "R5") (pin "2") (pinfunction "2_2") (pintype "passive"))
    )
    (net (code "61") (name "Net-(OK2-A)") (class "Default")
      (node (ref "OK2") (pin "1") (pinfunction "A_1") (pintype "passive"))
      (node (ref "R11") (pin "1") (pinfunction "1_1") (pintype "passive"))
    )
    (net (code "62") (name "Net-(OK2-C)") (class "Default")
      (node (ref "LED3") (pin "A") (pinfunction "A_A") (pintype "passive"))
      (node (ref "OK2") (pin "2") (pinfunction "C_2") (pintype "passive"))
    )
    (net (code "63") (name "Net-(OK2-EMIT)") (class "Default")
      (node (ref "OK2") (pin "3") (pinfunction "EMIT_3") (pintype "passive"))
      (node (ref "R10") (pin "2") (pinfunction "2_2") (pintype "passive"))
    )
    (net (code "64") (name "Net-(OK3-A)") (class "Default")
      (node (ref "OK3") (pin "1") (pinfunction "A_1") (pintype "passive"))
      (node (ref "R15") (pin "1") (pinfunction "1_1") (pintype "passive"))
    )
    (net (code "65") (name "Net-(OK3-C)") (class "Default")
      (node (ref "LED4") (pin "A") (pinfunction "A_A") (pintype "passive"))
      (node (ref "OK3") (pin "2") (pinfunction "C_2") (pintype "passive"))
    )
    (net (code "66") (name "Net-(OK3-EMIT)") (class "Default")
      (node (ref "OK3") (pin "3") (pinfunction "EMIT_3") (pintype "passive"))
      (node (ref "R14") (pin "2") (pinfunction "2_2") (pintype "passive"))
    )
    (net (code "67") (name "Net-(OK4-A)") (class "Default")
      (node (ref "OK4") (pin "1") (pinfunction "A_1") (pintype "passive"))
      (node (ref "R18") (pin "1") (pinfunction "1_1") (pintype "passive"))
    )
    (net (code "68") (name "Net-(OK4-C)") (class "Default")
      (node (ref "LED5") (pin "A") (pinfunction "A_A") (pintype "passive"))
      (node (ref "OK4") (pin "2") (pinfunction "C_2") (pintype "passive"))
    )
    (net (code "69") (name "Net-(OK4-EMIT)") (class "Default")
      (node (ref "OK4") (pin "3") (pinfunction "EMIT_3") (pintype "passive"))
      (node (ref "R17") (pin "2") (pinfunction "2_2") (pintype "passive"))
    )
    (net (code "70") (name "Net-(OK5-A)") (class "Default")
      (node (ref "OK5") (pin "1") (pinfunction "A_1") (pintype "passive"))
      (node (ref "R20") (pin "1") (pinfunction "1_1") (pintype "passive"))
    )
    (net (code "71") (name "Net-(OK5-C)") (class "Default")
      (node (ref "LED6") (pin "A") (pinfunction "A_A") (pintype "passive"))
      (node (ref "OK5") (pin "2") (pinfunction "C_2") (pintype "passive"))
    )
    (net (code "72") (name "Net-(OK5-EMIT)") (class "Default")
      (node (ref "OK5") (pin "3") (pinfunction "EMIT_3") (pintype "passive"))
      (node (ref "R19") (pin "2") (pinfunction "2_2") (pintype "passive"))
    )
    (net (code "73") (name "Net-(OK6-A)") (class "Default")
      (node (ref "OK6") (pin "1") (pinfunction "A_1") (pintype "passive"))
      (node (ref "R22") (pin "1") (pinfunction "1_1") (pintype "passive"))
    )
    (net (code "74") (name "Net-(OK6-C)") (class "Default")
      (node (ref "LED7") (pin "A") (pinfunction "A_A") (pintype "passive"))
      (node (ref "OK6") (pin "2") (pinfunction "C_2") (pintype "passive"))
    )
    (net (code "75") (name "Net-(OK6-EMIT)") (class "Default")
      (node (ref "OK6") (pin "3") (pinfunction "EMIT_3") (pintype "passive"))
      (node (ref "R21") (pin "2") (pinfunction "2_2") (pintype "passive"))
    )
    (net (code "76") (name "Net-(OK7-A)") (class "Default")
      (node (ref "OK7") (pin "1") (pinfunction "A_1") (pintype "passive"))
      (node (ref "R24") (pin "1") (pinfunction "1_1") (pintype "passive"))
    )
    (net (code "77") (name "Net-(OK7-C)") (class "Default")
      (node (ref "LED8") (pin "A") (pinfunction "A_A") (pintype "passive"))
      (node (ref "OK7") (pin "2") (pinfunction "C_2") (pintype "passive"))
    )
    (net (code "78") (name "Net-(OK7-EMIT)") (class "Default")
      (node (ref "OK7") (pin "3") (pinfunction "EMIT_3") (pintype "passive"))
      (node (ref "R23") (pin "2") (pinfunction "2_2") (pintype "passive"))
    )
    (net (code "79") (name "Net-(OK8-A)") (class "Default")
      (node (ref "OK8") (pin "1") (pinfunction "A_1") (pintype "passive"))
      (node (ref "R32") (pin "1") (pinfunction "1_1") (pintype "passive"))
    )
    (net (code "80") (name "Net-(OK8-C)") (class "Default")
      (node (ref "LED9") (pin "A") (pinfunction "A_A") (pintype "passive"))
      (node (ref "OK8") (pin "2") (pinfunction "C_2") (pintype "passive"))
    )
    (net (code "81") (name "Net-(OK8-EMIT)") (class "Default")
      (node (ref "OK8") (pin "3") (pinfunction "EMIT_3") (pintype "passive"))
      (node (ref "R27") (pin "2") (pinfunction "2_2") (pintype "passive"))
    )
    (net (code "82") (name "Net-(R5-Pad1)") (class "Default")
      (node (ref "R5") (pin "1") (pinfunction "1_1") (pintype "passive"))
      (node (ref "T2") (pin "B") (pinfunction "B_B") (pintype "passive"))
    )
    (net (code "83") (name "Net-(R10-Pad1)") (class "Default")
      (node (ref "R10") (pin "1") (pinfunction "1_1") (pintype "passive"))
      (node (ref "T1") (pin "B") (pinfunction "B_B") (pintype "passive"))
    )
    (net (code "84") (name "Net-(R14-Pad1)") (class "Default")
      (node (ref "R14") (pin "1") (pinfunction "1_1") (pintype "passive"))
      (node (ref "T3") (pin "B") (pinfunction "B_B") (pintype "passive"))
    )
    (net (code "85") (name "Net-(R17-Pad1)") (class "Default")
      (node (ref "R17") (pin "1") (pinfunction "1_1") (pintype "passive"))
      (node (ref "T4") (pin "B") (pinfunction "B_B") (pintype "passive"))
    )
    (net (code "86") (name "Net-(R19-Pad1)") (class "Default")
      (node (ref "R19") (pin "1") (pinfunction "1_1") (pintype "passive"))
      (node (ref "T5") (pin "B") (pinfunction "B_B") (pintype "passive"))
    )
    (net (code "87") (name "Net-(R21-Pad1)") (class "Default")
      (node (ref "R21") (pin "1") (pinfunction "1_1") (pintype "passive"))
      (node (ref "T6") (pin "B") (pinfunction "B_B") (pintype "passive"))
    )
    (net (code "88") (name "Net-(R23-Pad1)") (class "Default")
      (node (ref "R23") (pin "1") (pinfunction "1_1") (pintype "passive"))
      (node (ref "T7") (pin "B") (pinfunction "B_B") (pintype "passive"))
    )
    (net (code "89") (name "Net-(R25-Pad1)") (class "Default")
      (node (ref "R25") (pin "1") (pinfunction "1_1") (pintype "passive"))
      (node (ref "U5") (pin "CH_PD") (pinfunction "CH_PD_CH_PD") (pintype "bidirectional"))
    )
    (net (code "90") (name "Net-(R27-Pad1)") (class "Default")
      (node (ref "R27") (pin "1") (pinfunction "1_1") (pintype "passive"))
      (node (ref "T8") (pin "B") (pinfunction "B_B") (pintype "passive"))
    )
    (net (code "91") (name "Net-(R28-Pad1)") (class "Default")
      (node (ref "R28") (pin "1") (pinfunction "1_1") (pintype "passive"))
      (node (ref "U$5") (pin "1") (pinfunction "1_1") (pintype "passive"))
      (node (ref "U$5") (pin "2") (pinfunction "2_2") (pintype "passive"))
      (node (ref "U5") (pin "GPIO0") (pinfunction "GPIO0_GPIO0") (pintype "bidirectional"))
    )
    (net (code "92") (name "Net-(R29-Pad2)") (class "Default")
      (node (ref "R29") (pin "2") (pinfunction "2_2") (pintype "passive"))
      (node (ref "U5") (pin "GPIO15") (pinfunction "GPIO15_GPIO15") (pintype "bidirectional"))
    )
    (net (code "93") (name "Net-(U5-RX)") (class "Default")
      (node (ref "R30") (pin "2") (pinfunction "2_2") (pintype "passive"))
      (node (ref "R31") (pin "1") (pinfunction "1_1") (pintype "passive"))
      (node (ref "U5") (pin "RXD0") (pinfunction "RX_RXD0") (pintype "bidirectional"))
    )
    (net (code "94") (name "VCC") (class "Default")
      (node (ref "C1") (pin "1") (pinfunction "1_1") (pintype "passive"))
      (node (ref "C3") (pin "1") (pinfunction "1_1") (pintype "passive"))
      (node (ref "D1") (pin "C") (pinfunction "C_C") (pintype "passive"))
      (node (ref "D2") (pin "C") (pinfunction "C_C") (pintype "passive"))
      (node (ref "D3") (pin "C") (pinfunction "C_C") (pintype "passive"))
      (node (ref "D4") (pin "C") (pinfunction "C_C") (pintype "passive"))
      (node (ref "D5") (pin "C") (pinfunction "C_C") (pintype "passive"))
      (node (ref "D6") (pin "C") (pinfunction "C_C") (pintype "passive"))
      (node (ref "D7") (pin "C") (pinfunction "C_C") (pintype "passive"))
      (node (ref "D8") (pin "C") (pinfunction "C_C") (pintype "passive"))
      (node (ref "HLK1") (pin "P$3") (pinfunction "-VO_P$3") (pintype "bidirectional"))
      (node (ref "J8") (pin "1") (pinfunction "1_1") (pintype "passive"))
      (node (ref "K1") (pin "1") (pinfunction "1_1") (pintype "passive"))
      (node (ref "K2") (pin "1") (pinfunction "1_1") (pintype "passive"))
      (node (ref "K3") (pin "1") (pinfunction "1_1") (pintype "passive"))
      (node (ref "K4") (pin "1") (pinfunction "1_1") (pintype "passive"))
      (node (ref "K5") (pin "1") (pinfunction "1_1") (pintype "passive"))
      (node (ref "K6") (pin "1") (pinfunction "1_1") (pintype "passive"))
      (node (ref "K7") (pin "1") (pinfunction "1_1") (pintype "passive"))
      (node (ref "K8") (pin "1") (pinfunction "1_1") (pintype "passive"))
      (node (ref "LED1") (pin "A") (pinfunction "A_A") (pintype "passive"))
      (node (ref "OK1") (pin "4") (pinfunction "COL_4") (pintype "passive"))
      (node (ref "OK2") (pin "4") (pinfunction "COL_4") (pintype "passive"))
      (node (ref "OK3") (pin "4") (pinfunction "COL_4") (pintype "passive"))
      (node (ref "OK4") (pin "4") (pinfunction "COL_4") (pintype "passive"))
      (node (ref "OK5") (pin "4") (pinfunction "COL_4") (pintype "passive"))
      (node (ref "OK6") (pin "4") (pinfunction "COL_4") (pintype "passive"))
      (node (ref "OK7") (pin "4") (pinfunction "COL_4") (pintype "passive"))
      (node (ref "OK8") (pin "4") (pinfunction "COL_4") (pintype "passive"))
      (node (ref "U4") (pin "3") (pinfunction "IN_3") (pintype "input"))
    )
    (net (code "95") (name "unconnected-(IC3-INTA-Pad20)") (class "Default")
      (node (ref "IC3") (pin "20") (pinfunction "INTA_20") (pintype "output"))
    )
    (net (code "96") (name "unconnected-(IC3-INTB-Pad19)") (class "Default")
      (node (ref "IC3") (pin "19") (pinfunction "INTB_19") (pintype "output"))
    )
    (net (code "97") (name "unconnected-(K1B-O-PadNC)") (class "Default")
      (node (ref "K1") (pin "NC") (pinfunction "O_NC") (pintype "passive"))
    )
    (net (code "98") (name "unconnected-(K2B-O-PadNC)") (class "Default")
      (node (ref "K2") (pin "NC") (pinfunction "O_NC") (pintype "passive"))
    )
    (net (code "99") (name "unconnected-(K3B-O-PadNC)") (class "Default")
      (node (ref "K3") (pin "NC") (pinfunction "O_NC") (pintype "passive"))
    )
    (net (code "100") (name "unconnected-(K4B-O-PadNC)") (class "Default")
      (node (ref "K4") (pin "NC") (pinfunction "O_NC") (pintype "passive"))
    )
    (net (code "101") (name "unconnected-(K5B-O-PadNC)") (class "Default")
      (node (ref "K5") (pin "NC") (pinfunction "O_NC") (pintype "passive"))
    )
    (net (code "102") (name "unconnected-(K6B-O-PadNC)") (class "Default")
      (node (ref "K6") (pin "NC") (pinfunction "O_NC") (pintype "passive"))
    )
    (net (code "103") (name "unconnected-(K7B-O-PadNC)") (class "Default")
      (node (ref "K7") (pin "NC") (pinfunction "O_NC") (pintype "passive"))
    )
    (net (code "104") (name "unconnected-(K8B-O-PadNC)") (class "Default")
      (node (ref "K8") (pin "NC") (pinfunction "O_NC") (pintype "passive"))
    )
    (net (code "105") (name "unconnected-(U5-*GPIO9-PadGPIO9)") (class "Default")
      (node (ref "U5") (pin "GPIO9") (pinfunction "*GPIO9_GPIO9") (pintype "bidirectional"))
    )
    (net (code "106") (name "unconnected-(U5-*GPIO10-PadGPIO10)") (class "Default")
      (node (ref "U5") (pin "GPIO10") (pinfunction "*GPIO10_GPIO10") (pintype "bidirectional"))
    )
    (net (code "107") (name "unconnected-(U5-PadCS0)") (class "Default")
      (node (ref "U5") (pin "CS0") (pinfunction "CS0_CS0") (pintype "bidirectional"))
    )
    (net (code "108") (name "unconnected-(U5-PadMISO)") (class "Default")
      (node (ref "U5") (pin "MISO") (pinfunction "MISO_MISO") (pintype "bidirectional"))
    )
    (net (code "109") (name "unconnected-(U5-PadMOSI)") (class "Default")
      (node (ref "U5") (pin "MOSI") (pinfunction "MOSI_MOSI") (pintype "bidirectional"))
    )
    (net (code "110") (name "unconnected-(U5-PadSCLK)") (class "Default")
      (node (ref "U5") (pin "SCLK") (pinfunction "SCLK_SCLK") (pintype "bidirectional"))
    )
  )
)
